# RGBM-01.net
KiCad netlist of a schematic drawn in Altium Designer
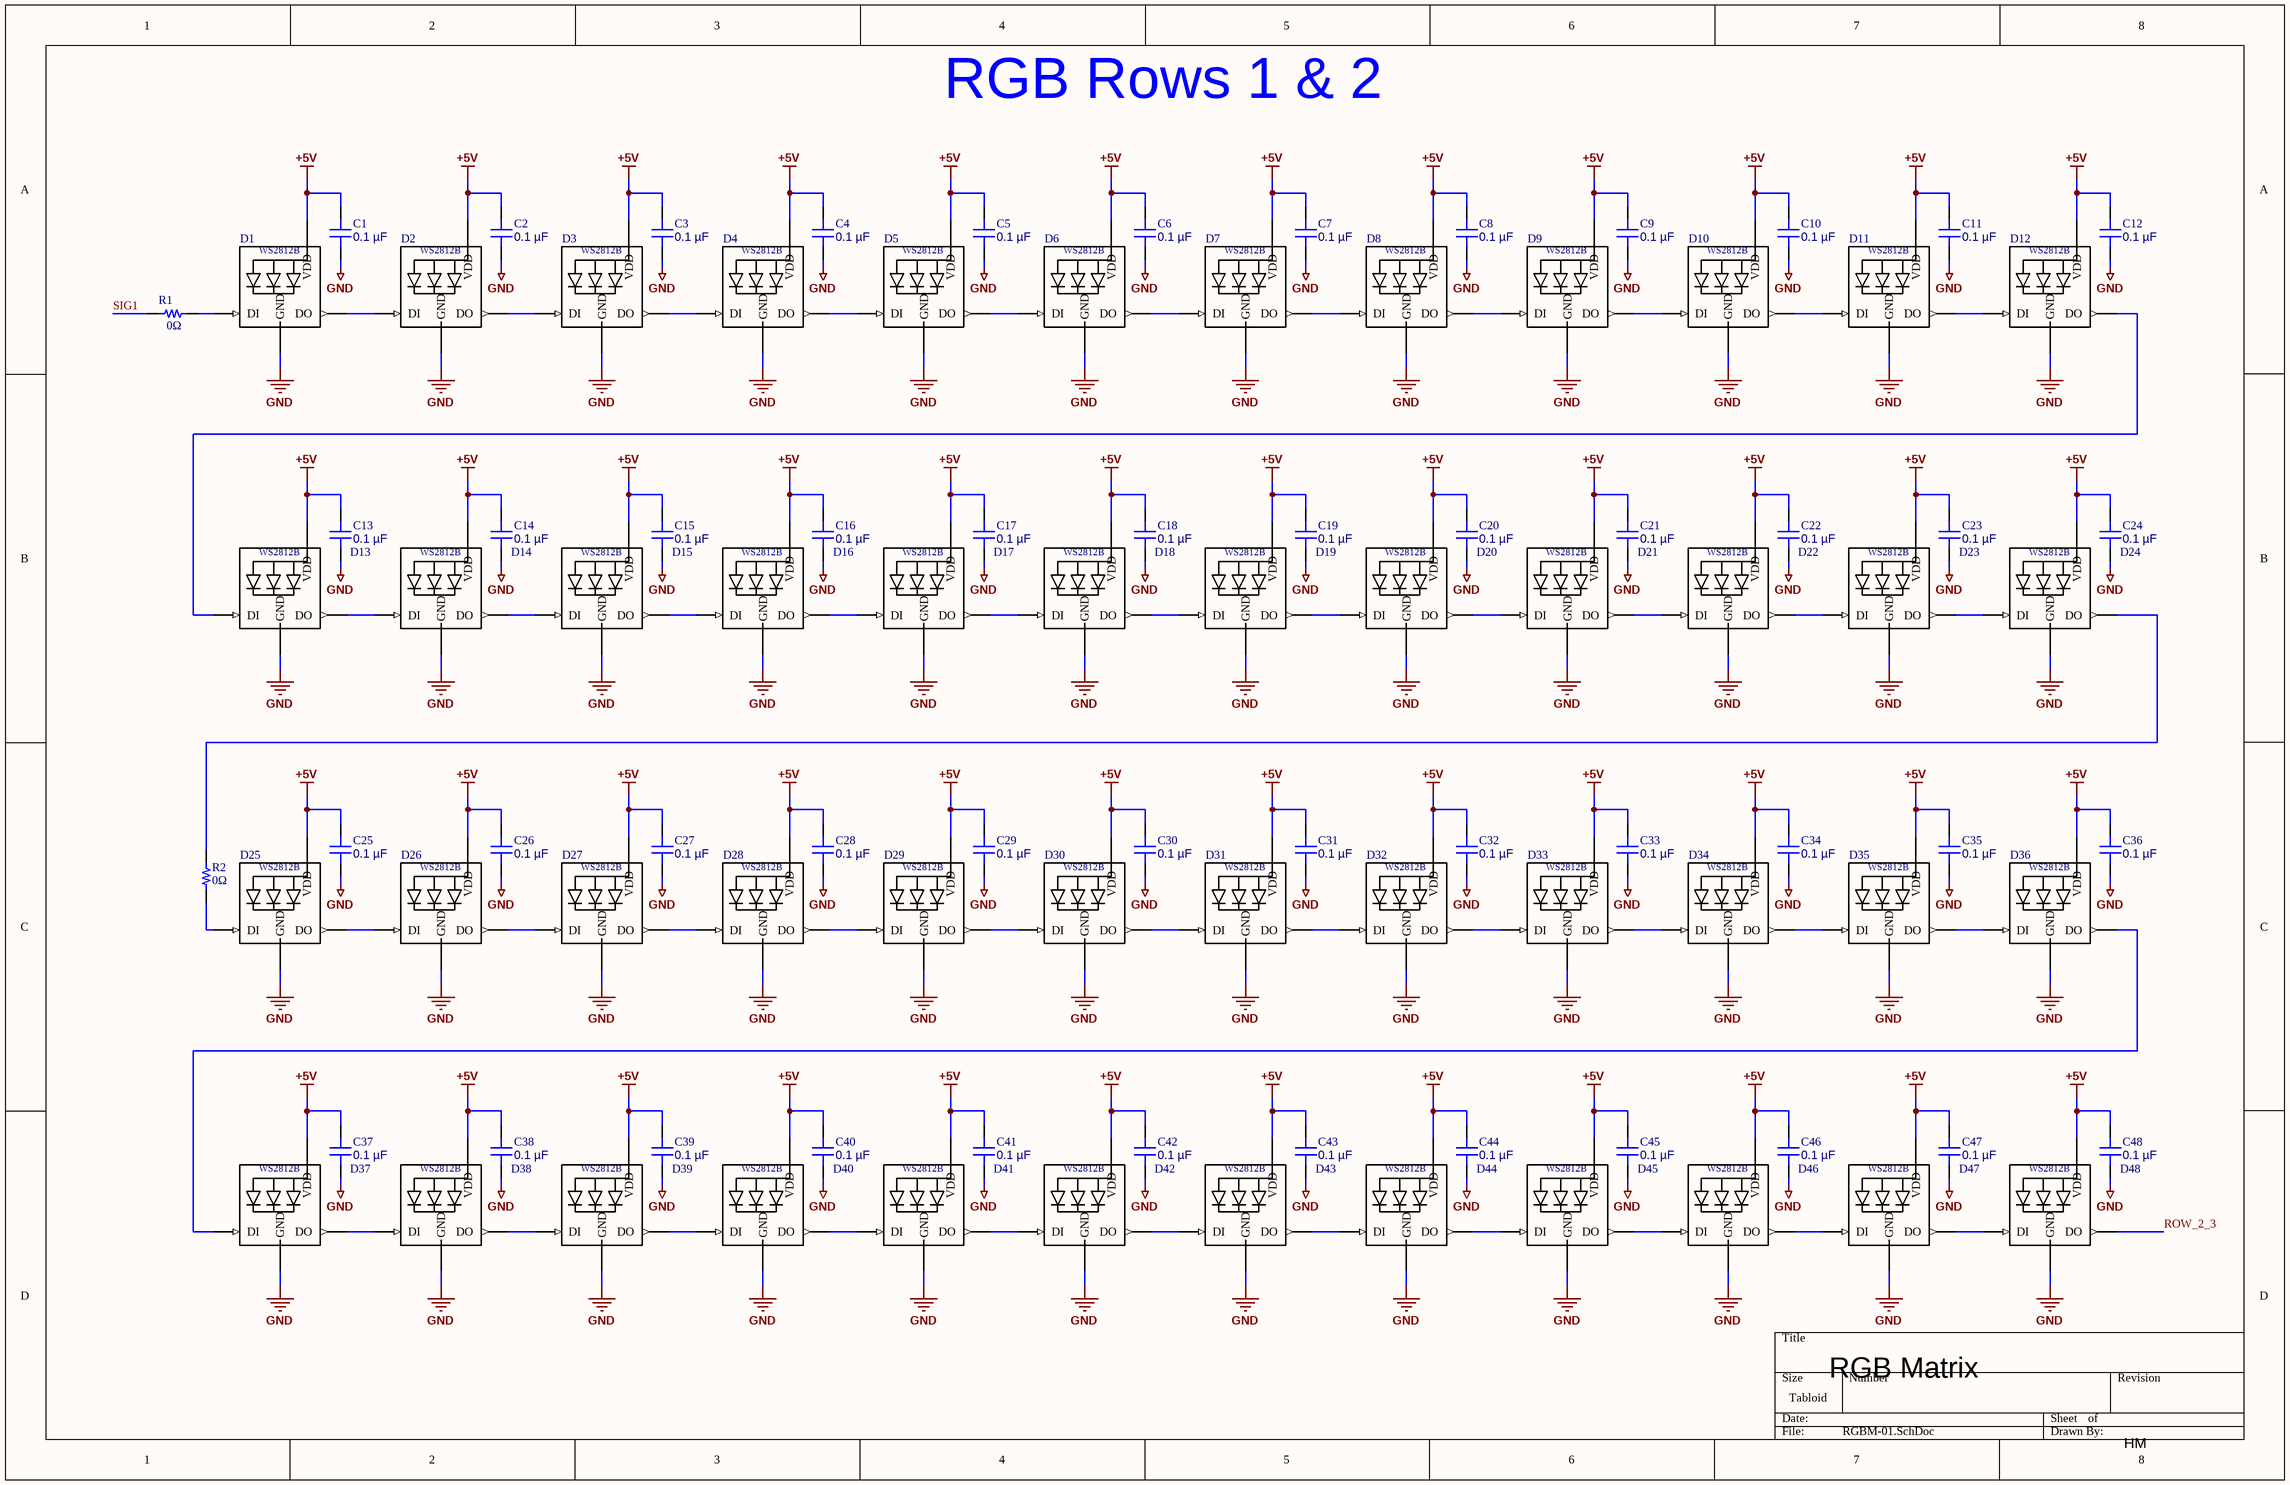
[diagram p0: RGBM-01.SchDoc]

(export (version "E")
  (design (tool "Eeschema 10.0.6"))
  (components
    (comp (ref "C1")
      (value "0.1 µF")
      (footprint "CAP 0603_1608")
      (description "CAP CER 0.1UF 50V X7R 0603")
      (fields
        (field (name "PART NUMBER") "C0603C104K5RAC7411")
        (field (name "CAPACITANCE") "0.1 µF")
        (field (name "MANUFACTURER") "KEMET")
      )
      (libsource (lib "Celestial Altium Library - altium_library") (part "Capacitor"))
    )
    (comp (ref "C2")
      (value "0.1 µF")
      (footprint "CAP 0603_1608")
      (description "CAP CER 0.1UF 50V X7R 0603")
      (fields
        (field (name "PART NUMBER") "C0603C104K5RAC7411")
        (field (name "CAPACITANCE") "0.1 µF")
        (field (name "MANUFACTURER") "KEMET")
      )
      (libsource (lib "Celestial Altium Library - altium_library") (part "Capacitor"))
    )
    (comp (ref "C3")
      (value "0.1 µF")
      (footprint "CAP 0603_1608")
      (description "CAP CER 0.1UF 50V X7R 0603")
      (fields
        (field (name "PART NUMBER") "C0603C104K5RAC7411")
        (field (name "CAPACITANCE") "0.1 µF")
        (field (name "MANUFACTURER") "KEMET")
      )
      (libsource (lib "Celestial Altium Library - altium_library") (part "Capacitor"))
    )
    (comp (ref "C4")
      (value "0.1 µF")
      (footprint "CAP 0603_1608")
      (description "CAP CER 0.1UF 50V X7R 0603")
      (fields
        (field (name "PART NUMBER") "C0603C104K5RAC7411")
        (field (name "CAPACITANCE") "0.1 µF")
        (field (name "MANUFACTURER") "KEMET")
      )
      (libsource (lib "Celestial Altium Library - altium_library") (part "Capacitor"))
    )
    (comp (ref "C5")
      (value "0.1 µF")
      (footprint "CAP 0603_1608")
      (description "CAP CER 0.1UF 50V X7R 0603")
      (fields
        (field (name "PART NUMBER") "C0603C104K5RAC7411")
        (field (name "CAPACITANCE") "0.1 µF")
        (field (name "MANUFACTURER") "KEMET")
      )
      (libsource (lib "Celestial Altium Library - altium_library") (part "Capacitor"))
    )
    (comp (ref "C6")
      (value "0.1 µF")
      (footprint "CAP 0603_1608")
      (description "CAP CER 0.1UF 50V X7R 0603")
      (fields
        (field (name "PART NUMBER") "C0603C104K5RAC7411")
        (field (name "CAPACITANCE") "0.1 µF")
        (field (name "MANUFACTURER") "KEMET")
      )
      (libsource (lib "Celestial Altium Library - altium_library") (part "Capacitor"))
    )
    (comp (ref "C7")
      (value "0.1 µF")
      (footprint "CAP 0603_1608")
      (description "CAP CER 0.1UF 50V X7R 0603")
      (fields
        (field (name "PART NUMBER") "C0603C104K5RAC7411")
        (field (name "CAPACITANCE") "0.1 µF")
        (field (name "MANUFACTURER") "KEMET")
      )
      (libsource (lib "Celestial Altium Library - altium_library") (part "Capacitor"))
    )
    (comp (ref "C8")
      (value "0.1 µF")
      (footprint "CAP 0603_1608")
      (description "CAP CER 0.1UF 50V X7R 0603")
      (fields
        (field (name "PART NUMBER") "C0603C104K5RAC7411")
        (field (name "CAPACITANCE") "0.1 µF")
        (field (name "MANUFACTURER") "KEMET")
      )
      (libsource (lib "Celestial Altium Library - altium_library") (part "Capacitor"))
    )
    (comp (ref "C9")
      (value "0.1 µF")
      (footprint "CAP 0603_1608")
      (description "CAP CER 0.1UF 50V X7R 0603")
      (fields
        (field (name "PART NUMBER") "C0603C104K5RAC7411")
        (field (name "CAPACITANCE") "0.1 µF")
        (field (name "MANUFACTURER") "KEMET")
      )
      (libsource (lib "Celestial Altium Library - altium_library") (part "Capacitor"))
    )
    (comp (ref "C10")
      (value "0.1 µF")
      (footprint "CAP 0603_1608")
      (description "CAP CER 0.1UF 50V X7R 0603")
      (fields
        (field (name "PART NUMBER") "C0603C104K5RAC7411")
        (field (name "CAPACITANCE") "0.1 µF")
        (field (name "MANUFACTURER") "KEMET")
      )
      (libsource (lib "Celestial Altium Library - altium_library") (part "Capacitor"))
    )
    (comp (ref "C11")
      (value "0.1 µF")
      (footprint "CAP 0603_1608")
      (description "CAP CER 0.1UF 50V X7R 0603")
      (fields
        (field (name "PART NUMBER") "C0603C104K5RAC7411")
        (field (name "CAPACITANCE") "0.1 µF")
        (field (name "MANUFACTURER") "KEMET")
      )
      (libsource (lib "Celestial Altium Library - altium_library") (part "Capacitor"))
    )
    (comp (ref "C12")
      (value "0.1 µF")
      (footprint "CAP 0603_1608")
      (description "CAP CER 0.1UF 50V X7R 0603")
      (fields
        (field (name "PART NUMBER") "C0603C104K5RAC7411")
        (field (name "CAPACITANCE") "0.1 µF")
        (field (name "MANUFACTURER") "KEMET")
      )
      (libsource (lib "Celestial Altium Library - altium_library") (part "Capacitor"))
    )
    (comp (ref "C13")
      (value "0.1 µF")
      (footprint "CAP 0603_1608")
      (description "CAP CER 0.1UF 50V X7R 0603")
      (fields
        (field (name "PART NUMBER") "C0603C104K5RAC7411")
        (field (name "CAPACITANCE") "0.1 µF")
        (field (name "MANUFACTURER") "KEMET")
      )
      (libsource (lib "Celestial Altium Library - altium_library") (part "Capacitor"))
    )
    (comp (ref "C14")
      (value "0.1 µF")
      (footprint "CAP 0603_1608")
      (description "CAP CER 0.1UF 50V X7R 0603")
      (fields
        (field (name "PART NUMBER") "C0603C104K5RAC7411")
        (field (name "CAPACITANCE") "0.1 µF")
        (field (name "MANUFACTURER") "KEMET")
      )
      (libsource (lib "Celestial Altium Library - altium_library") (part "Capacitor"))
    )
    (comp (ref "C15")
      (value "0.1 µF")
      (footprint "CAP 0603_1608")
      (description "CAP CER 0.1UF 50V X7R 0603")
      (fields
        (field (name "PART NUMBER") "C0603C104K5RAC7411")
        (field (name "CAPACITANCE") "0.1 µF")
        (field (name "MANUFACTURER") "KEMET")
      )
      (libsource (lib "Celestial Altium Library - altium_library") (part "Capacitor"))
    )
    (comp (ref "C16")
      (value "0.1 µF")
      (footprint "CAP 0603_1608")
      (description "CAP CER 0.1UF 50V X7R 0603")
      (fields
        (field (name "PART NUMBER") "C0603C104K5RAC7411")
        (field (name "CAPACITANCE") "0.1 µF")
        (field (name "MANUFACTURER") "KEMET")
      )
      (libsource (lib "Celestial Altium Library - altium_library") (part "Capacitor"))
    )
    (comp (ref "C17")
      (value "0.1 µF")
      (footprint "CAP 0603_1608")
      (description "CAP CER 0.1UF 50V X7R 0603")
      (fields
        (field (name "PART NUMBER") "C0603C104K5RAC7411")
        (field (name "CAPACITANCE") "0.1 µF")
        (field (name "MANUFACTURER") "KEMET")
      )
      (libsource (lib "Celestial Altium Library - altium_library") (part "Capacitor"))
    )
    (comp (ref "C18")
      (value "0.1 µF")
      (footprint "CAP 0603_1608")
      (description "CAP CER 0.1UF 50V X7R 0603")
      (fields
        (field (name "PART NUMBER") "C0603C104K5RAC7411")
        (field (name "CAPACITANCE") "0.1 µF")
        (field (name "MANUFACTURER") "KEMET")
      )
      (libsource (lib "Celestial Altium Library - altium_library") (part "Capacitor"))
    )
    (comp (ref "C19")
      (value "0.1 µF")
      (footprint "CAP 0603_1608")
      (description "CAP CER 0.1UF 50V X7R 0603")
      (fields
        (field (name "PART NUMBER") "C0603C104K5RAC7411")
        (field (name "CAPACITANCE") "0.1 µF")
        (field (name "MANUFACTURER") "KEMET")
      )
      (libsource (lib "Celestial Altium Library - altium_library") (part "Capacitor"))
    )
    (comp (ref "C20")
      (value "0.1 µF")
      (footprint "CAP 0603_1608")
      (description "CAP CER 0.1UF 50V X7R 0603")
      (fields
        (field (name "PART NUMBER") "C0603C104K5RAC7411")
        (field (name "CAPACITANCE") "0.1 µF")
        (field (name "MANUFACTURER") "KEMET")
      )
      (libsource (lib "Celestial Altium Library - altium_library") (part "Capacitor"))
    )
    (comp (ref "C21")
      (value "0.1 µF")
      (footprint "CAP 0603_1608")
      (description "CAP CER 0.1UF 50V X7R 0603")
      (fields
        (field (name "PART NUMBER") "C0603C104K5RAC7411")
        (field (name "CAPACITANCE") "0.1 µF")
        (field (name "MANUFACTURER") "KEMET")
      )
      (libsource (lib "Celestial Altium Library - altium_library") (part "Capacitor"))
    )
    (comp (ref "C22")
      (value "0.1 µF")
      (footprint "CAP 0603_1608")
      (description "CAP CER 0.1UF 50V X7R 0603")
      (fields
        (field (name "PART NUMBER") "C0603C104K5RAC7411")
        (field (name "CAPACITANCE") "0.1 µF")
        (field (name "MANUFACTURER") "KEMET")
      )
      (libsource (lib "Celestial Altium Library - altium_library") (part "Capacitor"))
    )
    (comp (ref "C23")
      (value "0.1 µF")
      (footprint "CAP 0603_1608")
      (description "CAP CER 0.1UF 50V X7R 0603")
      (fields
        (field (name "PART NUMBER") "C0603C104K5RAC7411")
        (field (name "CAPACITANCE") "0.1 µF")
        (field (name "MANUFACTURER") "KEMET")
      )
      (libsource (lib "Celestial Altium Library - altium_library") (part "Capacitor"))
    )
    (comp (ref "C24")
      (value "0.1 µF")
      (footprint "CAP 0603_1608")
      (description "CAP CER 0.1UF 50V X7R 0603")
      (fields
        (field (name "PART NUMBER") "C0603C104K5RAC7411")
        (field (name "CAPACITANCE") "0.1 µF")
        (field (name "MANUFACTURER") "KEMET")
      )
      (libsource (lib "Celestial Altium Library - altium_library") (part "Capacitor"))
    )
    (comp (ref "C25")
      (value "0.1 µF")
      (footprint "CAP 0603_1608")
      (description "CAP CER 0.1UF 50V X7R 0603")
      (fields
        (field (name "PART NUMBER") "C0603C104K5RAC7411")
        (field (name "CAPACITANCE") "0.1 µF")
        (field (name "MANUFACTURER") "KEMET")
      )
      (libsource (lib "Celestial Altium Library - altium_library") (part "Capacitor"))
    )
    (comp (ref "C26")
      (value "0.1 µF")
      (footprint "CAP 0603_1608")
      (description "CAP CER 0.1UF 50V X7R 0603")
      (fields
        (field (name "PART NUMBER") "C0603C104K5RAC7411")
        (field (name "CAPACITANCE") "0.1 µF")
        (field (name "MANUFACTURER") "KEMET")
      )
      (libsource (lib "Celestial Altium Library - altium_library") (part "Capacitor"))
    )
    (comp (ref "C27")
      (value "0.1 µF")
      (footprint "CAP 0603_1608")
      (description "CAP CER 0.1UF 50V X7R 0603")
      (fields
        (field (name "PART NUMBER") "C0603C104K5RAC7411")
        (field (name "CAPACITANCE") "0.1 µF")
        (field (name "MANUFACTURER") "KEMET")
      )
      (libsource (lib "Celestial Altium Library - altium_library") (part "Capacitor"))
    )
    (comp (ref "C28")
      (value "0.1 µF")
      (footprint "CAP 0603_1608")
      (description "CAP CER 0.1UF 50V X7R 0603")
      (fields
        (field (name "PART NUMBER") "C0603C104K5RAC7411")
        (field (name "CAPACITANCE") "0.1 µF")
        (field (name "MANUFACTURER") "KEMET")
      )
      (libsource (lib "Celestial Altium Library - altium_library") (part "Capacitor"))
    )
    (comp (ref "C29")
      (value "0.1 µF")
      (footprint "CAP 0603_1608")
      (description "CAP CER 0.1UF 50V X7R 0603")
      (fields
        (field (name "PART NUMBER") "C0603C104K5RAC7411")
        (field (name "CAPACITANCE") "0.1 µF")
        (field (name "MANUFACTURER") "KEMET")
      )
      (libsource (lib "Celestial Altium Library - altium_library") (part "Capacitor"))
    )
    (comp (ref "C30")
      (value "0.1 µF")
      (footprint "CAP 0603_1608")
      (description "CAP CER 0.1UF 50V X7R 0603")
      (fields
        (field (name "PART NUMBER") "C0603C104K5RAC7411")
        (field (name "CAPACITANCE") "0.1 µF")
        (field (name "MANUFACTURER") "KEMET")
      )
      (libsource (lib "Celestial Altium Library - altium_library") (part "Capacitor"))
    )
    (comp (ref "C31")
      (value "0.1 µF")
      (footprint "CAP 0603_1608")
      (description "CAP CER 0.1UF 50V X7R 0603")
      (fields
        (field (name "PART NUMBER") "C0603C104K5RAC7411")
        (field (name "CAPACITANCE") "0.1 µF")
        (field (name "MANUFACTURER") "KEMET")
      )
      (libsource (lib "Celestial Altium Library - altium_library") (part "Capacitor"))
    )
    (comp (ref "C32")
      (value "0.1 µF")
      (footprint "CAP 0603_1608")
      (description "CAP CER 0.1UF 50V X7R 0603")
      (fields
        (field (name "PART NUMBER") "C0603C104K5RAC7411")
        (field (name "CAPACITANCE") "0.1 µF")
        (field (name "MANUFACTURER") "KEMET")
      )
      (libsource (lib "Celestial Altium Library - altium_library") (part "Capacitor"))
    )
    (comp (ref "C33")
      (value "0.1 µF")
      (footprint "CAP 0603_1608")
      (description "CAP CER 0.1UF 50V X7R 0603")
      (fields
        (field (name "PART NUMBER") "C0603C104K5RAC7411")
        (field (name "CAPACITANCE") "0.1 µF")
        (field (name "MANUFACTURER") "KEMET")
      )
      (libsource (lib "Celestial Altium Library - altium_library") (part "Capacitor"))
    )
    (comp (ref "C34")
      (value "0.1 µF")
      (footprint "CAP 0603_1608")
      (description "CAP CER 0.1UF 50V X7R 0603")
      (fields
        (field (name "PART NUMBER") "C0603C104K5RAC7411")
        (field (name "CAPACITANCE") "0.1 µF")
        (field (name "MANUFACTURER") "KEMET")
      )
      (libsource (lib "Celestial Altium Library - altium_library") (part "Capacitor"))
    )
    (comp (ref "C35")
      (value "0.1 µF")
      (footprint "CAP 0603_1608")
      (description "CAP CER 0.1UF 50V X7R 0603")
      (fields
        (field (name "PART NUMBER") "C0603C104K5RAC7411")
        (field (name "CAPACITANCE") "0.1 µF")
        (field (name "MANUFACTURER") "KEMET")
      )
      (libsource (lib "Celestial Altium Library - altium_library") (part "Capacitor"))
    )
    (comp (ref "C36")
      (value "0.1 µF")
      (footprint "CAP 0603_1608")
      (description "CAP CER 0.1UF 50V X7R 0603")
      (fields
        (field (name "PART NUMBER") "C0603C104K5RAC7411")
        (field (name "CAPACITANCE") "0.1 µF")
        (field (name "MANUFACTURER") "KEMET")
      )
      (libsource (lib "Celestial Altium Library - altium_library") (part "Capacitor"))
    )
    (comp (ref "C37")
      (value "0.1 µF")
      (footprint "CAP 0603_1608")
      (description "CAP CER 0.1UF 50V X7R 0603")
      (fields
        (field (name "PART NUMBER") "C0603C104K5RAC7411")
        (field (name "CAPACITANCE") "0.1 µF")
        (field (name "MANUFACTURER") "KEMET")
      )
      (libsource (lib "Celestial Altium Library - altium_library") (part "Capacitor"))
    )
    (comp (ref "C38")
      (value "0.1 µF")
      (footprint "CAP 0603_1608")
      (description "CAP CER 0.1UF 50V X7R 0603")
      (fields
        (field (name "PART NUMBER") "C0603C104K5RAC7411")
        (field (name "CAPACITANCE") "0.1 µF")
        (field (name "MANUFACTURER") "KEMET")
      )
      (libsource (lib "Celestial Altium Library - altium_library") (part "Capacitor"))
    )
    (comp (ref "C39")
      (value "0.1 µF")
      (footprint "CAP 0603_1608")
      (description "CAP CER 0.1UF 50V X7R 0603")
      (fields
        (field (name "PART NUMBER") "C0603C104K5RAC7411")
        (field (name "CAPACITANCE") "0.1 µF")
        (field (name "MANUFACTURER") "KEMET")
      )
      (libsource (lib "Celestial Altium Library - altium_library") (part "Capacitor"))
    )
    (comp (ref "C40")
      (value "0.1 µF")
      (footprint "CAP 0603_1608")
      (description "CAP CER 0.1UF 50V X7R 0603")
      (fields
        (field (name "PART NUMBER") "C0603C104K5RAC7411")
        (field (name "CAPACITANCE") "0.1 µF")
        (field (name "MANUFACTURER") "KEMET")
      )
      (libsource (lib "Celestial Altium Library - altium_library") (part "Capacitor"))
    )
    (comp (ref "C41")
      (value "0.1 µF")
      (footprint "CAP 0603_1608")
      (description "CAP CER 0.1UF 50V X7R 0603")
      (fields
        (field (name "PART NUMBER") "C0603C104K5RAC7411")
        (field (name "CAPACITANCE") "0.1 µF")
        (field (name "MANUFACTURER") "KEMET")
      )
      (libsource (lib "Celestial Altium Library - altium_library") (part "Capacitor"))
    )
    (comp (ref "C42")
      (value "0.1 µF")
      (footprint "CAP 0603_1608")
      (description "CAP CER 0.1UF 50V X7R 0603")
      (fields
        (field (name "PART NUMBER") "C0603C104K5RAC7411")
        (field (name "CAPACITANCE") "0.1 µF")
        (field (name "MANUFACTURER") "KEMET")
      )
      (libsource (lib "Celestial Altium Library - altium_library") (part "Capacitor"))
    )
    (comp (ref "C43")
      (value "0.1 µF")
      (footprint "CAP 0603_1608")
      (description "CAP CER 0.1UF 50V X7R 0603")
      (fields
        (field (name "PART NUMBER") "C0603C104K5RAC7411")
        (field (name "CAPACITANCE") "0.1 µF")
        (field (name "MANUFACTURER") "KEMET")
      )
      (libsource (lib "Celestial Altium Library - altium_library") (part "Capacitor"))
    )
    (comp (ref "C44")
      (value "0.1 µF")
      (footprint "CAP 0603_1608")
      (description "CAP CER 0.1UF 50V X7R 0603")
      (fields
        (field (name "PART NUMBER") "C0603C104K5RAC7411")
        (field (name "CAPACITANCE") "0.1 µF")
        (field (name "MANUFACTURER") "KEMET")
      )
      (libsource (lib "Celestial Altium Library - altium_library") (part "Capacitor"))
    )
    (comp (ref "C45")
      (value "0.1 µF")
      (footprint "CAP 0603_1608")
      (description "CAP CER 0.1UF 50V X7R 0603")
      (fields
        (field (name "PART NUMBER") "C0603C104K5RAC7411")
        (field (name "CAPACITANCE") "0.1 µF")
        (field (name "MANUFACTURER") "KEMET")
      )
      (libsource (lib "Celestial Altium Library - altium_library") (part "Capacitor"))
    )
    (comp (ref "C46")
      (value "0.1 µF")
      (footprint "CAP 0603_1608")
      (description "CAP CER 0.1UF 50V X7R 0603")
      (fields
        (field (name "PART NUMBER") "C0603C104K5RAC7411")
        (field (name "CAPACITANCE") "0.1 µF")
        (field (name "MANUFACTURER") "KEMET")
      )
      (libsource (lib "Celestial Altium Library - altium_library") (part "Capacitor"))
    )
    (comp (ref "C47")
      (value "0.1 µF")
      (footprint "CAP 0603_1608")
      (description "CAP CER 0.1UF 50V X7R 0603")
      (fields
        (field (name "PART NUMBER") "C0603C104K5RAC7411")
        (field (name "CAPACITANCE") "0.1 µF")
        (field (name "MANUFACTURER") "KEMET")
      )
      (libsource (lib "Celestial Altium Library - altium_library") (part "Capacitor"))
    )
    (comp (ref "C48")
      (value "0.1 µF")
      (footprint "CAP 0603_1608")
      (description "CAP CER 0.1UF 50V X7R 0603")
      (fields
        (field (name "PART NUMBER") "C0603C104K5RAC7411")
        (field (name "CAPACITANCE") "0.1 µF")
        (field (name "MANUFACTURER") "KEMET")
      )
      (libsource (lib "Celestial Altium Library - altium_library") (part "Capacitor"))
    )
    (comp (ref "D1")
      (value "WS2812B")
      (footprint "*WS2812B_WS2812B(Primary)")
      (description "Intelligent control LED integrated light source")
      (fields (field (name "MF") "Worldsemi"))
      (libsource (lib "WS2812B") (part "WS2812B"))
    )
    (comp (ref "D2")
      (value "WS2812B")
      (footprint "*WS2812B_WS2812B(Primary)")
      (description "Intelligent control LED integrated light source")
      (fields (field (name "MF") "Worldsemi"))
      (libsource (lib "WS2812B") (part "WS2812B"))
    )
    (comp (ref "D3")
      (value "WS2812B")
      (footprint "*WS2812B_WS2812B(Primary)")
      (description "Intelligent control LED integrated light source")
      (fields (field (name "MF") "Worldsemi"))
      (libsource (lib "WS2812B") (part "WS2812B"))
    )
    (comp (ref "D4")
      (value "WS2812B")
      (footprint "*WS2812B_WS2812B(Primary)")
      (description "Intelligent control LED integrated light source")
      (fields (field (name "MF") "Worldsemi"))
      (libsource (lib "WS2812B") (part "WS2812B"))
    )
    (comp (ref "D5")
      (value "WS2812B")
      (footprint "*WS2812B_WS2812B(Primary)")
      (description "Intelligent control LED integrated light source")
      (fields (field (name "MF") "Worldsemi"))
      (libsource (lib "WS2812B") (part "WS2812B"))
    )
    (comp (ref "D6")
      (value "WS2812B")
      (footprint "*WS2812B_WS2812B(Primary)")
      (description "Intelligent control LED integrated light source")
      (fields (field (name "MF") "Worldsemi"))
      (libsource (lib "WS2812B") (part "WS2812B"))
    )
    (comp (ref "D7")
      (value "WS2812B")
      (footprint "*WS2812B_WS2812B(Primary)")
      (description "Intelligent control LED integrated light source")
      (fields (field (name "MF") "Worldsemi"))
      (libsource (lib "WS2812B") (part "WS2812B"))
    )
    (comp (ref "D8")
      (value "WS2812B")
      (footprint "*WS2812B_WS2812B(Primary)")
      (description "Intelligent control LED integrated light source")
      (fields (field (name "MF") "Worldsemi"))
      (libsource (lib "WS2812B") (part "WS2812B"))
    )
    (comp (ref "D9")
      (value "WS2812B")
      (footprint "*WS2812B_WS2812B(Primary)")
      (description "Intelligent control LED integrated light source")
      (fields (field (name "MF") "Worldsemi"))
      (libsource (lib "WS2812B") (part "WS2812B"))
    )
    (comp (ref "D10")
      (value "WS2812B")
      (footprint "*WS2812B_WS2812B(Primary)")
      (description "Intelligent control LED integrated light source")
      (fields (field (name "MF") "Worldsemi"))
      (libsource (lib "WS2812B") (part "WS2812B"))
    )
    (comp (ref "D11")
      (value "WS2812B")
      (footprint "*WS2812B_WS2812B(Primary)")
      (description "Intelligent control LED integrated light source")
      (fields (field (name "MF") "Worldsemi"))
      (libsource (lib "WS2812B") (part "WS2812B"))
    )
    (comp (ref "D12")
      (value "WS2812B")
      (footprint "*WS2812B_WS2812B(Primary)")
      (description "Intelligent control LED integrated light source")
      (fields (field (name "MF") "Worldsemi"))
      (libsource (lib "WS2812B") (part "WS2812B"))
    )
    (comp (ref "D13")
      (value "WS2812B")
      (footprint "*WS2812B_WS2812B(Primary)")
      (description "Intelligent control LED integrated light source")
      (fields (field (name "MF") "Worldsemi"))
      (libsource (lib "WS2812B") (part "WS2812B"))
    )
    (comp (ref "D14")
      (value "WS2812B")
      (footprint "*WS2812B_WS2812B(Primary)")
      (description "Intelligent control LED integrated light source")
      (fields (field (name "MF") "Worldsemi"))
      (libsource (lib "WS2812B") (part "WS2812B"))
    )
    (comp (ref "D15")
      (value "WS2812B")
      (footprint "*WS2812B_WS2812B(Primary)")
      (description "Intelligent control LED integrated light source")
      (fields (field (name "MF") "Worldsemi"))
      (libsource (lib "WS2812B") (part "WS2812B"))
    )
    (comp (ref "D16")
      (value "WS2812B")
      (footprint "*WS2812B_WS2812B(Primary)")
      (description "Intelligent control LED integrated light source")
      (fields (field (name "MF") "Worldsemi"))
      (libsource (lib "WS2812B") (part "WS2812B"))
    )
    (comp (ref "D17")
      (value "WS2812B")
      (footprint "*WS2812B_WS2812B(Primary)")
      (description "Intelligent control LED integrated light source")
      (fields (field (name "MF") "Worldsemi"))
      (libsource (lib "WS2812B") (part "WS2812B"))
    )
    (comp (ref "D18")
      (value "WS2812B")
      (footprint "*WS2812B_WS2812B(Primary)")
      (description "Intelligent control LED integrated light source")
      (fields (field (name "MF") "Worldsemi"))
      (libsource (lib "WS2812B") (part "WS2812B"))
    )
    (comp (ref "D19")
      (value "WS2812B")
      (footprint "*WS2812B_WS2812B(Primary)")
      (description "Intelligent control LED integrated light source")
      (fields (field (name "MF") "Worldsemi"))
      (libsource (lib "WS2812B") (part "WS2812B"))
    )
    (comp (ref "D20")
      (value "WS2812B")
      (footprint "*WS2812B_WS2812B(Primary)")
      (description "Intelligent control LED integrated light source")
      (fields (field (name "MF") "Worldsemi"))
      (libsource (lib "WS2812B") (part "WS2812B"))
    )
    (comp (ref "D21")
      (value "WS2812B")
      (footprint "*WS2812B_WS2812B(Primary)")
      (description "Intelligent control LED integrated light source")
      (fields (field (name "MF") "Worldsemi"))
      (libsource (lib "WS2812B") (part "WS2812B"))
    )
    (comp (ref "D22")
      (value "WS2812B")
      (footprint "*WS2812B_WS2812B(Primary)")
      (description "Intelligent control LED integrated light source")
      (fields (field (name "MF") "Worldsemi"))
      (libsource (lib "WS2812B") (part "WS2812B"))
    )
    (comp (ref "D23")
      (value "WS2812B")
      (footprint "*WS2812B_WS2812B(Primary)")
      (description "Intelligent control LED integrated light source")
      (fields (field (name "MF") "Worldsemi"))
      (libsource (lib "WS2812B") (part "WS2812B"))
    )
    (comp (ref "D24")
      (value "WS2812B")
      (footprint "*WS2812B_WS2812B(Primary)")
      (description "Intelligent control LED integrated light source")
      (fields (field (name "MF") "Worldsemi"))
      (libsource (lib "WS2812B") (part "WS2812B"))
    )
    (comp (ref "D25")
      (value "WS2812B")
      (footprint "*WS2812B_WS2812B(Primary)")
      (description "Intelligent control LED integrated light source")
      (fields (field (name "MF") "Worldsemi"))
      (libsource (lib "WS2812B") (part "WS2812B"))
    )
    (comp (ref "D26")
      (value "WS2812B")
      (footprint "*WS2812B_WS2812B(Primary)")
      (description "Intelligent control LED integrated light source")
      (fields (field (name "MF") "Worldsemi"))
      (libsource (lib "WS2812B") (part "WS2812B"))
    )
    (comp (ref "D27")
      (value "WS2812B")
      (footprint "*WS2812B_WS2812B(Primary)")
      (description "Intelligent control LED integrated light source")
      (fields (field (name "MF") "Worldsemi"))
      (libsource (lib "WS2812B") (part "WS2812B"))
    )
    (comp (ref "D28")
      (value "WS2812B")
      (footprint "*WS2812B_WS2812B(Primary)")
      (description "Intelligent control LED integrated light source")
      (fields (field (name "MF") "Worldsemi"))
      (libsource (lib "WS2812B") (part "WS2812B"))
    )
    (comp (ref "D29")
      (value "WS2812B")
      (footprint "*WS2812B_WS2812B(Primary)")
      (description "Intelligent control LED integrated light source")
      (fields (field (name "MF") "Worldsemi"))
      (libsource (lib "WS2812B") (part "WS2812B"))
    )
    (comp (ref "D30")
      (value "WS2812B")
      (footprint "*WS2812B_WS2812B(Primary)")
      (description "Intelligent control LED integrated light source")
      (fields (field (name "MF") "Worldsemi"))
      (libsource (lib "WS2812B") (part "WS2812B"))
    )
    (comp (ref "D31")
      (value "WS2812B")
      (footprint "*WS2812B_WS2812B(Primary)")
      (description "Intelligent control LED integrated light source")
      (fields (field (name "MF") "Worldsemi"))
      (libsource (lib "WS2812B") (part "WS2812B"))
    )
    (comp (ref "D32")
      (value "WS2812B")
      (footprint "*WS2812B_WS2812B(Primary)")
      (description "Intelligent control LED integrated light source")
      (fields (field (name "MF") "Worldsemi"))
      (libsource (lib "WS2812B") (part "WS2812B"))
    )
    (comp (ref "D33")
      (value "WS2812B")
      (footprint "*WS2812B_WS2812B(Primary)")
      (description "Intelligent control LED integrated light source")
      (fields (field (name "MF") "Worldsemi"))
      (libsource (lib "WS2812B") (part "WS2812B"))
    )
    (comp (ref "D34")
      (value "WS2812B")
      (footprint "*WS2812B_WS2812B(Primary)")
      (description "Intelligent control LED integrated light source")
      (fields (field (name "MF") "Worldsemi"))
      (libsource (lib "WS2812B") (part "WS2812B"))
    )
    (comp (ref "D35")
      (value "WS2812B")
      (footprint "*WS2812B_WS2812B(Primary)")
      (description "Intelligent control LED integrated light source")
      (fields (field (name "MF") "Worldsemi"))
      (libsource (lib "WS2812B") (part "WS2812B"))
    )
    (comp (ref "D36")
      (value "WS2812B")
      (footprint "*WS2812B_WS2812B(Primary)")
      (description "Intelligent control LED integrated light source")
      (fields (field (name "MF") "Worldsemi"))
      (libsource (lib "WS2812B") (part "WS2812B"))
    )
    (comp (ref "D37")
      (value "WS2812B")
      (footprint "*WS2812B_WS2812B(Primary)")
      (description "Intelligent control LED integrated light source")
      (fields (field (name "MF") "Worldsemi"))
      (libsource (lib "WS2812B") (part "WS2812B"))
    )
    (comp (ref "D38")
      (value "WS2812B")
      (footprint "*WS2812B_WS2812B(Primary)")
      (description "Intelligent control LED integrated light source")
      (fields (field (name "MF") "Worldsemi"))
      (libsource (lib "WS2812B") (part "WS2812B"))
    )
    (comp (ref "D39")
      (value "WS2812B")
      (footprint "*WS2812B_WS2812B(Primary)")
      (description "Intelligent control LED integrated light source")
      (fields (field (name "MF") "Worldsemi"))
      (libsource (lib "WS2812B") (part "WS2812B"))
    )
    (comp (ref "D40")
      (value "WS2812B")
      (footprint "*WS2812B_WS2812B(Primary)")
      (description "Intelligent control LED integrated light source")
      (fields (field (name "MF") "Worldsemi"))
      (libsource (lib "WS2812B") (part "WS2812B"))
    )
    (comp (ref "D41")
      (value "WS2812B")
      (footprint "*WS2812B_WS2812B(Primary)")
      (description "Intelligent control LED integrated light source")
      (fields (field (name "MF") "Worldsemi"))
      (libsource (lib "WS2812B") (part "WS2812B"))
    )
    (comp (ref "D42")
      (value "WS2812B")
      (footprint "*WS2812B_WS2812B(Primary)")
      (description "Intelligent control LED integrated light source")
      (fields (field (name "MF") "Worldsemi"))
      (libsource (lib "WS2812B") (part "WS2812B"))
    )
    (comp (ref "D43")
      (value "WS2812B")
      (footprint "*WS2812B_WS2812B(Primary)")
      (description "Intelligent control LED integrated light source")
      (fields (field (name "MF") "Worldsemi"))
      (libsource (lib "WS2812B") (part "WS2812B"))
    )
    (comp (ref "D44")
      (value "WS2812B")
      (footprint "*WS2812B_WS2812B(Primary)")
      (description "Intelligent control LED integrated light source")
      (fields (field (name "MF") "Worldsemi"))
      (libsource (lib "WS2812B") (part "WS2812B"))
    )
    (comp (ref "D45")
      (value "WS2812B")
      (footprint "*WS2812B_WS2812B(Primary)")
      (description "Intelligent control LED integrated light source")
      (fields (field (name "MF") "Worldsemi"))
      (libsource (lib "WS2812B") (part "WS2812B"))
    )
    (comp (ref "D46")
      (value "WS2812B")
      (footprint "*WS2812B_WS2812B(Primary)")
      (description "Intelligent control LED integrated light source")
      (fields (field (name "MF") "Worldsemi"))
      (libsource (lib "WS2812B") (part "WS2812B"))
    )
    (comp (ref "D47")
      (value "WS2812B")
      (footprint "*WS2812B_WS2812B(Primary)")
      (description "Intelligent control LED integrated light source")
      (fields (field (name "MF") "Worldsemi"))
      (libsource (lib "WS2812B") (part "WS2812B"))
    )
    (comp (ref "D48")
      (value "WS2812B")
      (footprint "*WS2812B_WS2812B(Primary)")
      (description "Intelligent control LED integrated light source")
      (fields (field (name "MF") "Worldsemi"))
      (libsource (lib "WS2812B") (part "WS2812B"))
    )
    (comp (ref "R1")
      (value "0Ω")
      (footprint "RES 0603_1608")
      (description "RES SMD 0 OHM JUMPER 0603")
      (fields (field (name "PART NUMBER") "YJP1608-R001") (field (name "MANUFACTURER") "Susumu"))
      (libsource (lib "Celestial Altium Library - altium_library") (part "Resistor"))
    )
    (comp (ref "R2")
      (value "0Ω")
      (footprint "RES 0603_1608")
      (description "RES SMD 0 OHM JUMPER 0603")
      (fields (field (name "PART NUMBER") "YJP1608-R001") (field (name "MANUFACTURER") "Susumu"))
      (libsource (lib "Celestial Altium Library - altium_library") (part "Resistor"))
    )
  )
  (nets
    (net (code "1") (name "+5V") (class "Default")
      (node (ref "C1") (pin "2") (pinfunction "2_2") (pintype "passive"))
      (node (ref "C10") (pin "2") (pinfunction "2_2") (pintype "passive"))
      (node (ref "C11") (pin "2") (pinfunction "2_2") (pintype "passive"))
      (node (ref "C12") (pin "2") (pinfunction "2_2") (pintype "passive"))
      (node (ref "C13") (pin "2") (pinfunction "2_2") (pintype "passive"))
      (node (ref "C14") (pin "2") (pinfunction "2_2") (pintype "passive"))
      (node (ref "C15") (pin "2") (pinfunction "2_2") (pintype "passive"))
      (node (ref "C16") (pin "2") (pinfunction "2_2") (pintype "passive"))
      (node (ref "C17") (pin "2") (pinfunction "2_2") (pintype "passive"))
      (node (ref "C18") (pin "2") (pinfunction "2_2") (pintype "passive"))
      (node (ref "C19") (pin "2") (pinfunction "2_2") (pintype "passive"))
      (node (ref "C2") (pin "2") (pinfunction "2_2") (pintype "passive"))
      (node (ref "C20") (pin "2") (pinfunction "2_2") (pintype "passive"))
      (node (ref "C21") (pin "2") (pinfunction "2_2") (pintype "passive"))
      (node (ref "C22") (pin "2") (pinfunction "2_2") (pintype "passive"))
      (node (ref "C23") (pin "2") (pinfunction "2_2") (pintype "passive"))
      (node (ref "C24") (pin "2") (pinfunction "2_2") (pintype "passive"))
      (node (ref "C25") (pin "2") (pinfunction "2_2") (pintype "passive"))
      (node (ref "C26") (pin "2") (pinfunction "2_2") (pintype "passive"))
      (node (ref "C27") (pin "2") (pinfunction "2_2") (pintype "passive"))
      (node (ref "C28") (pin "2") (pinfunction "2_2") (pintype "passive"))
      (node (ref "C29") (pin "2") (pinfunction "2_2") (pintype "passive"))
      (node (ref "C3") (pin "2") (pinfunction "2_2") (pintype "passive"))
      (node (ref "C30") (pin "2") (pinfunction "2_2") (pintype "passive"))
      (node (ref "C31") (pin "2") (pinfunction "2_2") (pintype "passive"))
      (node (ref "C32") (pin "2") (pinfunction "2_2") (pintype "passive"))
      (node (ref "C33") (pin "2") (pinfunction "2_2") (pintype "passive"))
      (node (ref "C34") (pin "2") (pinfunction "2_2") (pintype "passive"))
      (node (ref "C35") (pin "2") (pinfunction "2_2") (pintype "passive"))
      (node (ref "C36") (pin "2") (pinfunction "2_2") (pintype "passive"))
      (node (ref "C37") (pin "2") (pinfunction "2_2") (pintype "passive"))
      (node (ref "C38") (pin "2") (pinfunction "2_2") (pintype "passive"))
      (node (ref "C39") (pin "2") (pinfunction "2_2") (pintype "passive"))
      (node (ref "C4") (pin "2") (pinfunction "2_2") (pintype "passive"))
      (node (ref "C40") (pin "2") (pinfunction "2_2") (pintype "passive"))
      (node (ref "C41") (pin "2") (pinfunction "2_2") (pintype "passive"))
      (node (ref "C42") (pin "2") (pinfunction "2_2") (pintype "passive"))
      (node (ref "C43") (pin "2") (pinfunction "2_2") (pintype "passive"))
      (node (ref "C44") (pin "2") (pinfunction "2_2") (pintype "passive"))
      (node (ref "C45") (pin "2") (pinfunction "2_2") (pintype "passive"))
      (node (ref "C46") (pin "2") (pinfunction "2_2") (pintype "passive"))
      (node (ref "C47") (pin "2") (pinfunction "2_2") (pintype "passive"))
      (node (ref "C48") (pin "2") (pinfunction "2_2") (pintype "passive"))
      (node (ref "C5") (pin "2") (pinfunction "2_2") (pintype "passive"))
      (node (ref "C6") (pin "2") (pinfunction "2_2") (pintype "passive"))
      (node (ref "C7") (pin "2") (pinfunction "2_2") (pintype "passive"))
      (node (ref "C8") (pin "2") (pinfunction "2_2") (pintype "passive"))
      (node (ref "C9") (pin "2") (pinfunction "2_2") (pintype "passive"))
      (node (ref "D1") (pin "1-VDD") (pinfunction "VDD_1-VDD") (pintype "power_in"))
      (node (ref "D10") (pin "1-VDD") (pinfunction "VDD_1-VDD") (pintype "power_in"))
      (node (ref "D11") (pin "1-VDD") (pinfunction "VDD_1-VDD") (pintype "power_in"))
      (node (ref "D12") (pin "1-VDD") (pinfunction "VDD_1-VDD") (pintype "power_in"))
      (node (ref "D13") (pin "1-VDD") (pinfunction "VDD_1-VDD") (pintype "power_in"))
      (node (ref "D14") (pin "1-VDD") (pinfunction "VDD_1-VDD") (pintype "power_in"))
      (node (ref "D15") (pin "1-VDD") (pinfunction "VDD_1-VDD") (pintype "power_in"))
      (node (ref "D16") (pin "1-VDD") (pinfunction "VDD_1-VDD") (pintype "power_in"))
      (node (ref "D17") (pin "1-VDD") (pinfunction "VDD_1-VDD") (pintype "power_in"))
      (node (ref "D18") (pin "1-VDD") (pinfunction "VDD_1-VDD") (pintype "power_in"))
      (node (ref "D19") (pin "1-VDD") (pinfunction "VDD_1-VDD") (pintype "power_in"))
      (node (ref "D2") (pin "1-VDD") (pinfunction "VDD_1-VDD") (pintype "power_in"))
      (node (ref "D20") (pin "1-VDD") (pinfunction "VDD_1-VDD") (pintype "power_in"))
      (node (ref "D21") (pin "1-VDD") (pinfunction "VDD_1-VDD") (pintype "power_in"))
      (node (ref "D22") (pin "1-VDD") (pinfunction "VDD_1-VDD") (pintype "power_in"))
      (node (ref "D23") (pin "1-VDD") (pinfunction "VDD_1-VDD") (pintype "power_in"))
      (node (ref "D24") (pin "1-VDD") (pinfunction "VDD_1-VDD") (pintype "power_in"))
      (node (ref "D25") (pin "1-VDD") (pinfunction "VDD_1-VDD") (pintype "power_in"))
      (node (ref "D26") (pin "1-VDD") (pinfunction "VDD_1-VDD") (pintype "power_in"))
      (node (ref "D27") (pin "1-VDD") (pinfunction "VDD_1-VDD") (pintype "power_in"))
      (node (ref "D28") (pin "1-VDD") (pinfunction "VDD_1-VDD") (pintype "power_in"))
      (node (ref "D29") (pin "1-VDD") (pinfunction "VDD_1-VDD") (pintype "power_in"))
      (node (ref "D3") (pin "1-VDD") (pinfunction "VDD_1-VDD") (pintype "power_in"))
      (node (ref "D30") (pin "1-VDD") (pinfunction "VDD_1-VDD") (pintype "power_in"))
      (node (ref "D31") (pin "1-VDD") (pinfunction "VDD_1-VDD") (pintype "power_in"))
      (node (ref "D32") (pin "1-VDD") (pinfunction "VDD_1-VDD") (pintype "power_in"))
      (node (ref "D33") (pin "1-VDD") (pinfunction "VDD_1-VDD") (pintype "power_in"))
      (node (ref "D34") (pin "1-VDD") (pinfunction "VDD_1-VDD") (pintype "power_in"))
      (node (ref "D35") (pin "1-VDD") (pinfunction "VDD_1-VDD") (pintype "power_in"))
      (node (ref "D36") (pin "1-VDD") (pinfunction "VDD_1-VDD") (pintype "power_in"))
      (node (ref "D37") (pin "1-VDD") (pinfunction "VDD_1-VDD") (pintype "power_in"))
      (node (ref "D38") (pin "1-VDD") (pinfunction "VDD_1-VDD") (pintype "power_in"))
      (node (ref "D39") (pin "1-VDD") (pinfunction "VDD_1-VDD") (pintype "power_in"))
      (node (ref "D4") (pin "1-VDD") (pinfunction "VDD_1-VDD") (pintype "power_in"))
      (node (ref "D40") (pin "1-VDD") (pinfunction "VDD_1-VDD") (pintype "power_in"))
      (node (ref "D41") (pin "1-VDD") (pinfunction "VDD_1-VDD") (pintype "power_in"))
      (node (ref "D42") (pin "1-VDD") (pinfunction "VDD_1-VDD") (pintype "power_in"))
      (node (ref "D43") (pin "1-VDD") (pinfunction "VDD_1-VDD") (pintype "power_in"))
      (node (ref "D44") (pin "1-VDD") (pinfunction "VDD_1-VDD") (pintype "power_in"))
      (node (ref "D45") (pin "1-VDD") (pinfunction "VDD_1-VDD") (pintype "power_in"))
      (node (ref "D46") (pin "1-VDD") (pinfunction "VDD_1-VDD") (pintype "power_in"))
      (node (ref "D47") (pin "1-VDD") (pinfunction "VDD_1-VDD") (pintype "power_in"))
      (node (ref "D48") (pin "1-VDD") (pinfunction "VDD_1-VDD") (pintype "power_in"))
      (node (ref "D5") (pin "1-VDD") (pinfunction "VDD_1-VDD") (pintype "power_in"))
      (node (ref "D6") (pin "1-VDD") (pinfunction "VDD_1-VDD") (pintype "power_in"))
      (node (ref "D7") (pin "1-VDD") (pinfunction "VDD_1-VDD") (pintype "power_in"))
      (node (ref "D8") (pin "1-VDD") (pinfunction "VDD_1-VDD") (pintype "power_in"))
      (node (ref "D9") (pin "1-VDD") (pinfunction "VDD_1-VDD") (pintype "power_in"))
    )
    (net (code "2") (name "/ROW_2_3") (class "Default")
      (node (ref "D48") (pin "2-DOUT") (pinfunction "DO_2-DOUT") (pintype "output"))
    )
    (net (code "3") (name "/SIG1") (class "Default")
      (node (ref "R1") (pin "1") (pinfunction "1_1") (pintype "passive"))
    )
    (net (code "4") (name "GND") (class "Default")
      (node (ref "C1") (pin "1") (pinfunction "1_1") (pintype "passive"))
      (node (ref "C10") (pin "1") (pinfunction "1_1") (pintype "passive"))
      (node (ref "C11") (pin "1") (pinfunction "1_1") (pintype "passive"))
      (node (ref "C12") (pin "1") (pinfunction "1_1") (pintype "passive"))
      (node (ref "C13") (pin "1") (pinfunction "1_1") (pintype "passive"))
      (node (ref "C14") (pin "1") (pinfunction "1_1") (pintype "passive"))
      (node (ref "C15") (pin "1") (pinfunction "1_1") (pintype "passive"))
      (node (ref "C16") (pin "1") (pinfunction "1_1") (pintype "passive"))
      (node (ref "C17") (pin "1") (pinfunction "1_1") (pintype "passive"))
      (node (ref "C18") (pin "1") (pinfunction "1_1") (pintype "passive"))
      (node (ref "C19") (pin "1") (pinfunction "1_1") (pintype "passive"))
      (node (ref "C2") (pin "1") (pinfunction "1_1") (pintype "passive"))
      (node (ref "C20") (pin "1") (pinfunction "1_1") (pintype "passive"))
      (node (ref "C21") (pin "1") (pinfunction "1_1") (pintype "passive"))
      (node (ref "C22") (pin "1") (pinfunction "1_1") (pintype "passive"))
      (node (ref "C23") (pin "1") (pinfunction "1_1") (pintype "passive"))
      (node (ref "C24") (pin "1") (pinfunction "1_1") (pintype "passive"))
      (node (ref "C25") (pin "1") (pinfunction "1_1") (pintype "passive"))
      (node (ref "C26") (pin "1") (pinfunction "1_1") (pintype "passive"))
      (node (ref "C27") (pin "1") (pinfunction "1_1") (pintype "passive"))
      (node (ref "C28") (pin "1") (pinfunction "1_1") (pintype "passive"))
      (node (ref "C29") (pin "1") (pinfunction "1_1") (pintype "passive"))
      (node (ref "C3") (pin "1") (pinfunction "1_1") (pintype "passive"))
      (node (ref "C30") (pin "1") (pinfunction "1_1") (pintype "passive"))
      (node (ref "C31") (pin "1") (pinfunction "1_1") (pintype "passive"))
      (node (ref "C32") (pin "1") (pinfunction "1_1") (pintype "passive"))
      (node (ref "C33") (pin "1") (pinfunction "1_1") (pintype "passive"))
      (node (ref "C34") (pin "1") (pinfunction "1_1") (pintype "passive"))
      (node (ref "C35") (pin "1") (pinfunction "1_1") (pintype "passive"))
      (node (ref "C36") (pin "1") (pinfunction "1_1") (pintype "passive"))
      (node (ref "C37") (pin "1") (pinfunction "1_1") (pintype "passive"))
      (node (ref "C38") (pin "1") (pinfunction "1_1") (pintype "passive"))
      (node (ref "C39") (pin "1") (pinfunction "1_1") (pintype "passive"))
      (node (ref "C4") (pin "1") (pinfunction "1_1") (pintype "passive"))
      (node (ref "C40") (pin "1") (pinfunction "1_1") (pintype "passive"))
      (node (ref "C41") (pin "1") (pinfunction "1_1") (pintype "passive"))
      (node (ref "C42") (pin "1") (pinfunction "1_1") (pintype "passive"))
      (node (ref "C43") (pin "1") (pinfunction "1_1") (pintype "passive"))
      (node (ref "C44") (pin "1") (pinfunction "1_1") (pintype "passive"))
      (node (ref "C45") (pin "1") (pinfunction "1_1") (pintype "passive"))
      (node (ref "C46") (pin "1") (pinfunction "1_1") (pintype "passive"))
      (node (ref "C47") (pin "1") (pinfunction "1_1") (pintype "passive"))
      (node (ref "C48") (pin "1") (pinfunction "1_1") (pintype "passive"))
      (node (ref "C5") (pin "1") (pinfunction "1_1") (pintype "passive"))
      (node (ref "C6") (pin "1") (pinfunction "1_1") (pintype "passive"))
      (node (ref "C7") (pin "1") (pinfunction "1_1") (pintype "passive"))
      (node (ref "C8") (pin "1") (pinfunction "1_1") (pintype "passive"))
      (node (ref "C9") (pin "1") (pinfunction "1_1") (pintype "passive"))
      (node (ref "D1") (pin "3-GND") (pinfunction "GND_3-GND") (pintype "power_in"))
      (node (ref "D10") (pin "3-GND") (pinfunction "GND_3-GND") (pintype "power_in"))
      (node (ref "D11") (pin "3-GND") (pinfunction "GND_3-GND") (pintype "power_in"))
      (node (ref "D12") (pin "3-GND") (pinfunction "GND_3-GND") (pintype "power_in"))
      (node (ref "D13") (pin "3-GND") (pinfunction "GND_3-GND") (pintype "power_in"))
      (node (ref "D14") (pin "3-GND") (pinfunction "GND_3-GND") (pintype "power_in"))
      (node (ref "D15") (pin "3-GND") (pinfunction "GND_3-GND") (pintype "power_in"))
      (node (ref "D16") (pin "3-GND") (pinfunction "GND_3-GND") (pintype "power_in"))
      (node (ref "D17") (pin "3-GND") (pinfunction "GND_3-GND") (pintype "power_in"))
      (node (ref "D18") (pin "3-GND") (pinfunction "GND_3-GND") (pintype "power_in"))
      (node (ref "D19") (pin "3-GND") (pinfunction "GND_3-GND") (pintype "power_in"))
      (node (ref "D2") (pin "3-GND") (pinfunction "GND_3-GND") (pintype "power_in"))
      (node (ref "D20") (pin "3-GND") (pinfunction "GND_3-GND") (pintype "power_in"))
      (node (ref "D21") (pin "3-GND") (pinfunction "GND_3-GND") (pintype "power_in"))
      (node (ref "D22") (pin "3-GND") (pinfunction "GND_3-GND") (pintype "power_in"))
      (node (ref "D23") (pin "3-GND") (pinfunction "GND_3-GND") (pintype "power_in"))
      (node (ref "D24") (pin "3-GND") (pinfunction "GND_3-GND") (pintype "power_in"))
      (node (ref "D25") (pin "3-GND") (pinfunction "GND_3-GND") (pintype "power_in"))
      (node (ref "D26") (pin "3-GND") (pinfunction "GND_3-GND") (pintype "power_in"))
      (node (ref "D27") (pin "3-GND") (pinfunction "GND_3-GND") (pintype "power_in"))
      (node (ref "D28") (pin "3-GND") (pinfunction "GND_3-GND") (pintype "power_in"))
      (node (ref "D29") (pin "3-GND") (pinfunction "GND_3-GND") (pintype "power_in"))
      (node (ref "D3") (pin "3-GND") (pinfunction "GND_3-GND") (pintype "power_in"))
      (node (ref "D30") (pin "3-GND") (pinfunction "GND_3-GND") (pintype "power_in"))
      (node (ref "D31") (pin "3-GND") (pinfunction "GND_3-GND") (pintype "power_in"))
      (node (ref "D32") (pin "3-GND") (pinfunction "GND_3-GND") (pintype "power_in"))
      (node (ref "D33") (pin "3-GND") (pinfunction "GND_3-GND") (pintype "power_in"))
      (node (ref "D34") (pin "3-GND") (pinfunction "GND_3-GND") (pintype "power_in"))
      (node (ref "D35") (pin "3-GND") (pinfunction "GND_3-GND") (pintype "power_in"))
      (node (ref "D36") (pin "3-GND") (pinfunction "GND_3-GND") (pintype "power_in"))
      (node (ref "D37") (pin "3-GND") (pinfunction "GND_3-GND") (pintype "power_in"))
      (node (ref "D38") (pin "3-GND") (pinfunction "GND_3-GND") (pintype "power_in"))
      (node (ref "D39") (pin "3-GND") (pinfunction "GND_3-GND") (pintype "power_in"))
      (node (ref "D4") (pin "3-GND") (pinfunction "GND_3-GND") (pintype "power_in"))
      (node (ref "D40") (pin "3-GND") (pinfunction "GND_3-GND") (pintype "power_in"))
      (node (ref "D41") (pin "3-GND") (pinfunction "GND_3-GND") (pintype "power_in"))
      (node (ref "D42") (pin "3-GND") (pinfunction "GND_3-GND") (pintype "power_in"))
      (node (ref "D43") (pin "3-GND") (pinfunction "GND_3-GND") (pintype "power_in"))
      (node (ref "D44") (pin "3-GND") (pinfunction "GND_3-GND") (pintype "power_in"))
      (node (ref "D45") (pin "3-GND") (pinfunction "GND_3-GND") (pintype "power_in"))
      (node (ref "D46") (pin "3-GND") (pinfunction "GND_3-GND") (pintype "power_in"))
      (node (ref "D47") (pin "3-GND") (pinfunction "GND_3-GND") (pintype "power_in"))
      (node (ref "D48") (pin "3-GND") (pinfunction "GND_3-GND") (pintype "power_in"))
      (node (ref "D5") (pin "3-GND") (pinfunction "GND_3-GND") (pintype "power_in"))
      (node (ref "D6") (pin "3-GND") (pinfunction "GND_3-GND") (pintype "power_in"))
      (node (ref "D7") (pin "3-GND") (pinfunction "GND_3-GND") (pintype "power_in"))
      (node (ref "D8") (pin "3-GND") (pinfunction "GND_3-GND") (pintype "power_in"))
      (node (ref "D9") (pin "3-GND") (pinfunction "GND_3-GND") (pintype "power_in"))
    )
    (net (code "5") (name "Net-(D1-DI)") (class "Default")
      (node (ref "D1") (pin "4-DIN") (pinfunction "DI_4-DIN") (pintype "input"))
      (node (ref "R1") (pin "2") (pinfunction "2_2") (pintype "passive"))
    )
    (net (code "6") (name "Net-(D1-DO)") (class "Default")
      (node (ref "D1") (pin "2-DOUT") (pinfunction "DO_2-DOUT") (pintype "output"))
      (node (ref "D2") (pin "4-DIN") (pinfunction "DI_4-DIN") (pintype "input"))
    )
    (net (code "7") (name "Net-(D2-DO)") (class "Default")
      (node (ref "D2") (pin "2-DOUT") (pinfunction "DO_2-DOUT") (pintype "output"))
      (node (ref "D3") (pin "4-DIN") (pinfunction "DI_4-DIN") (pintype "input"))
    )
    (net (code "8") (name "Net-(D3-DO)") (class "Default")
      (node (ref "D3") (pin "2-DOUT") (pinfunction "DO_2-DOUT") (pintype "output"))
      (node (ref "D4") (pin "4-DIN") (pinfunction "DI_4-DIN") (pintype "input"))
    )
    (net (code "9") (name "Net-(D4-DO)") (class "Default")
      (node (ref "D4") (pin "2-DOUT") (pinfunction "DO_2-DOUT") (pintype "output"))
      (node (ref "D5") (pin "4-DIN") (pinfunction "DI_4-DIN") (pintype "input"))
    )
    (net (code "10") (name "Net-(D5-DO)") (class "Default")
      (node (ref "D5") (pin "2-DOUT") (pinfunction "DO_2-DOUT") (pintype "output"))
      (node (ref "D6") (pin "4-DIN") (pinfunction "DI_4-DIN") (pintype "input"))
    )
    (net (code "11") (name "Net-(D6-DO)") (class "Default")
      (node (ref "D6") (pin "2-DOUT") (pinfunction "DO_2-DOUT") (pintype "output"))
      (node (ref "D7") (pin "4-DIN") (pinfunction "DI_4-DIN") (pintype "input"))
    )
    (net (code "12") (name "Net-(D7-DO)") (class "Default")
      (node (ref "D7") (pin "2-DOUT") (pinfunction "DO_2-DOUT") (pintype "output"))
      (node (ref "D8") (pin "4-DIN") (pinfunction "DI_4-DIN") (pintype "input"))
    )
    (net (code "13") (name "Net-(D8-DO)") (class "Default")
      (node (ref "D8") (pin "2-DOUT") (pinfunction "DO_2-DOUT") (pintype "output"))
      (node (ref "D9") (pin "4-DIN") (pinfunction "DI_4-DIN") (pintype "input"))
    )
    (net (code "14") (name "Net-(D10-DI)") (class "Default")
      (node (ref "D10") (pin "4-DIN") (pinfunction "DI_4-DIN") (pintype "input"))
      (node (ref "D9") (pin "2-DOUT") (pinfunction "DO_2-DOUT") (pintype "output"))
    )
    (net (code "15") (name "Net-(D10-DO)") (class "Default")
      (node (ref "D10") (pin "2-DOUT") (pinfunction "DO_2-DOUT") (pintype "output"))
      (node (ref "D11") (pin "4-DIN") (pinfunction "DI_4-DIN") (pintype "input"))
    )
    (net (code "16") (name "Net-(D11-DO)") (class "Default")
      (node (ref "D11") (pin "2-DOUT") (pinfunction "DO_2-DOUT") (pintype "output"))
      (node (ref "D12") (pin "4-DIN") (pinfunction "DI_4-DIN") (pintype "input"))
    )
    (net (code "17") (name "Net-(D12-DO)") (class "Default")
      (node (ref "D12") (pin "2-DOUT") (pinfunction "DO_2-DOUT") (pintype "output"))
      (node (ref "D13") (pin "4-DIN") (pinfunction "DI_4-DIN") (pintype "input"))
    )
    (net (code "18") (name "Net-(D13-DO)") (class "Default")
      (node (ref "D13") (pin "2-DOUT") (pinfunction "DO_2-DOUT") (pintype "output"))
      (node (ref "D14") (pin "4-DIN") (pinfunction "DI_4-DIN") (pintype "input"))
    )
    (net (code "19") (name "Net-(D14-DO)") (class "Default")
      (node (ref "D14") (pin "2-DOUT") (pinfunction "DO_2-DOUT") (pintype "output"))
      (node (ref "D15") (pin "4-DIN") (pinfunction "DI_4-DIN") (pintype "input"))
    )
    (net (code "20") (name "Net-(D15-DO)") (class "Default")
      (node (ref "D15") (pin "2-DOUT") (pinfunction "DO_2-DOUT") (pintype "output"))
      (node (ref "D16") (pin "4-DIN") (pinfunction "DI_4-DIN") (pintype "input"))
    )
    (net (code "21") (name "Net-(D16-DO)") (class "Default")
      (node (ref "D16") (pin "2-DOUT") (pinfunction "DO_2-DOUT") (pintype "output"))
      (node (ref "D17") (pin "4-DIN") (pinfunction "DI_4-DIN") (pintype "input"))
    )
    (net (code "22") (name "Net-(D17-DO)") (class "Default")
      (node (ref "D17") (pin "2-DOUT") (pinfunction "DO_2-DOUT") (pintype "output"))
      (node (ref "D18") (pin "4-DIN") (pinfunction "DI_4-DIN") (pintype "input"))
    )
    (net (code "23") (name "Net-(D18-DO)") (class "Default")
      (node (ref "D18") (pin "2-DOUT") (pinfunction "DO_2-DOUT") (pintype "output"))
      (node (ref "D19") (pin "4-DIN") (pinfunction "DI_4-DIN") (pintype "input"))
    )
    (net (code "24") (name "Net-(D19-DO)") (class "Default")
      (node (ref "D19") (pin "2-DOUT") (pinfunction "DO_2-DOUT") (pintype "output"))
      (node (ref "D20") (pin "4-DIN") (pinfunction "DI_4-DIN") (pintype "input"))
    )
    (net (code "25") (name "Net-(D20-DO)") (class "Default")
      (node (ref "D20") (pin "2-DOUT") (pinfunction "DO_2-DOUT") (pintype "output"))
      (node (ref "D21") (pin "4-DIN") (pinfunction "DI_4-DIN") (pintype "input"))
    )
    (net (code "26") (name "Net-(D21-DO)") (class "Default")
      (node (ref "D21") (pin "2-DOUT") (pinfunction "DO_2-DOUT") (pintype "output"))
      (node (ref "D22") (pin "4-DIN") (pinfunction "DI_4-DIN") (pintype "input"))
    )
    (net (code "27") (name "Net-(D22-DO)") (class "Default")
      (node (ref "D22") (pin "2-DOUT") (pinfunction "DO_2-DOUT") (pintype "output"))
      (node (ref "D23") (pin "4-DIN") (pinfunction "DI_4-DIN") (pintype "input"))
    )
    (net (code "28") (name "Net-(D23-DO)") (class "Default")
      (node (ref "D23") (pin "2-DOUT") (pinfunction "DO_2-DOUT") (pintype "output"))
      (node (ref "D24") (pin "4-DIN") (pinfunction "DI_4-DIN") (pintype "input"))
    )
    (net (code "29") (name "Net-(D24-DO)") (class "Default")
      (node (ref "D24") (pin "2-DOUT") (pinfunction "DO_2-DOUT") (pintype "output"))
      (node (ref "R2") (pin "2") (pinfunction "2_2") (pintype "passive"))
    )
    (net (code "30") (name "Net-(D25-DI)") (class "Default")
      (node (ref "D25") (pin "4-DIN") (pinfunction "DI_4-DIN") (pintype "input"))
      (node (ref "R2") (pin "1") (pinfunction "1_1") (pintype "passive"))
    )
    (net (code "31") (name "Net-(D25-DO)") (class "Default")
      (node (ref "D25") (pin "2-DOUT") (pinfunction "DO_2-DOUT") (pintype "output"))
      (node (ref "D26") (pin "4-DIN") (pinfunction "DI_4-DIN") (pintype "input"))
    )
    (net (code "32") (name "Net-(D26-DO)") (class "Default")
      (node (ref "D26") (pin "2-DOUT") (pinfunction "DO_2-DOUT") (pintype "output"))
      (node (ref "D27") (pin "4-DIN") (pinfunction "DI_4-DIN") (pintype "input"))
    )
    (net (code "33") (name "Net-(D27-DO)") (class "Default")
      (node (ref "D27") (pin "2-DOUT") (pinfunction "DO_2-DOUT") (pintype "output"))
      (node (ref "D28") (pin "4-DIN") (pinfunction "DI_4-DIN") (pintype "input"))
    )
    (net (code "34") (name "Net-(D28-DO)") (class "Default")
      (node (ref "D28") (pin "2-DOUT") (pinfunction "DO_2-DOUT") (pintype "output"))
      (node (ref "D29") (pin "4-DIN") (pinfunction "DI_4-DIN") (pintype "input"))
    )
    (net (code "35") (name "Net-(D29-DO)") (class "Default")
      (node (ref "D29") (pin "2-DOUT") (pinfunction "DO_2-DOUT") (pintype "output"))
      (node (ref "D30") (pin "4-DIN") (pinfunction "DI_4-DIN") (pintype "input"))
    )
    (net (code "36") (name "Net-(D30-DO)") (class "Default")
      (node (ref "D30") (pin "2-DOUT") (pinfunction "DO_2-DOUT") (pintype "output"))
      (node (ref "D31") (pin "4-DIN") (pinfunction "DI_4-DIN") (pintype "input"))
    )
    (net (code "37") (name "Net-(D31-DO)") (class "Default")
      (node (ref "D31") (pin "2-DOUT") (pinfunction "DO_2-DOUT") (pintype "output"))
      (node (ref "D32") (pin "4-DIN") (pinfunction "DI_4-DIN") (pintype "input"))
    )
    (net (code "38") (name "Net-(D32-DO)") (class "Default")
      (node (ref "D32") (pin "2-DOUT") (pinfunction "DO_2-DOUT") (pintype "output"))
      (node (ref "D33") (pin "4-DIN") (pinfunction "DI_4-DIN") (pintype "input"))
    )
    (net (code "39") (name "Net-(D33-DO)") (class "Default")
      (node (ref "D33") (pin "2-DOUT") (pinfunction "DO_2-DOUT") (pintype "output"))
      (node (ref "D34") (pin "4-DIN") (pinfunction "DI_4-DIN") (pintype "input"))
    )
    (net (code "40") (name "Net-(D34-DO)") (class "Default")
      (node (ref "D34") (pin "2-DOUT") (pinfunction "DO_2-DOUT") (pintype "output"))
      (node (ref "D35") (pin "4-DIN") (pinfunction "DI_4-DIN") (pintype "input"))
    )
    (net (code "41") (name "Net-(D35-DO)") (class "Default")
      (node (ref "D35") (pin "2-DOUT") (pinfunction "DO_2-DOUT") (pintype "output"))
      (node (ref "D36") (pin "4-DIN") (pinfunction "DI_4-DIN") (pintype "input"))
    )
    (net (code "42") (name "Net-(D36-DO)") (class "Default")
      (node (ref "D36") (pin "2-DOUT") (pinfunction "DO_2-DOUT") (pintype "output"))
      (node (ref "D37") (pin "4-DIN") (pinfunction "DI_4-DIN") (pintype "input"))
    )
    (net (code "43") (name "Net-(D37-DO)") (class "Default")
      (node (ref "D37") (pin "2-DOUT") (pinfunction "DO_2-DOUT") (pintype "output"))
      (node (ref "D38") (pin "4-DIN") (pinfunction "DI_4-DIN") (pintype "input"))
    )
    (net (code "44") (name "Net-(D38-DO)") (class "Default")
      (node (ref "D38") (pin "2-DOUT") (pinfunction "DO_2-DOUT") (pintype "output"))
      (node (ref "D39") (pin "4-DIN") (pinfunction "DI_4-DIN") (pintype "input"))
    )
    (net (code "45") (name "Net-(D39-DO)") (class "Default")
      (node (ref "D39") (pin "2-DOUT") (pinfunction "DO_2-DOUT") (pintype "output"))
      (node (ref "D40") (pin "4-DIN") (pinfunction "DI_4-DIN") (pintype "input"))
    )
    (net (code "46") (name "Net-(D40-DO)") (class "Default")
      (node (ref "D40") (pin "2-DOUT") (pinfunction "DO_2-DOUT") (pintype "output"))
      (node (ref "D41") (pin "4-DIN") (pinfunction "DI_4-DIN") (pintype "input"))
    )
    (net (code "47") (name "Net-(D41-DO)") (class "Default")
      (node (ref "D41") (pin "2-DOUT") (pinfunction "DO_2-DOUT") (pintype "output"))
      (node (ref "D42") (pin "4-DIN") (pinfunction "DI_4-DIN") (pintype "input"))
    )
    (net (code "48") (name "Net-(D42-DO)") (class "Default")
      (node (ref "D42") (pin "2-DOUT") (pinfunction "DO_2-DOUT") (pintype "output"))
      (node (ref "D43") (pin "4-DIN") (pinfunction "DI_4-DIN") (pintype "input"))
    )
    (net (code "49") (name "Net-(D43-DO)") (class "Default")
      (node (ref "D43") (pin "2-DOUT") (pinfunction "DO_2-DOUT") (pintype "output"))
      (node (ref "D44") (pin "4-DIN") (pinfunction "DI_4-DIN") (pintype "input"))
    )
    (net (code "50") (name "Net-(D44-DO)") (class "Default")
      (node (ref "D44") (pin "2-DOUT") (pinfunction "DO_2-DOUT") (pintype "output"))
      (node (ref "D45") (pin "4-DIN") (pinfunction "DI_4-DIN") (pintype "input"))
    )
    (net (code "51") (name "Net-(D45-DO)") (class "Default")
      (node (ref "D45") (pin "2-DOUT") (pinfunction "DO_2-DOUT") (pintype "output"))
      (node (ref "D46") (pin "4-DIN") (pinfunction "DI_4-DIN") (pintype "input"))
    )
    (net (code "52") (name "Net-(D46-DO)") (class "Default")
      (node (ref "D46") (pin "2-DOUT") (pinfunction "DO_2-DOUT") (pintype "output"))
      (node (ref "D47") (pin "4-DIN") (pinfunction "DI_4-DIN") (pintype "input"))
    )
    (net (code "53") (name "Net-(D47-DO)") (class "Default")
      (node (ref "D47") (pin "2-DOUT") (pinfunction "DO_2-DOUT") (pintype "output"))
      (node (ref "D48") (pin "4-DIN") (pinfunction "DI_4-DIN") (pintype "input"))
    )
  )
)
